# P4_DSPBypass.net
KiCad netlist of a schematic drawn in Altium Designer
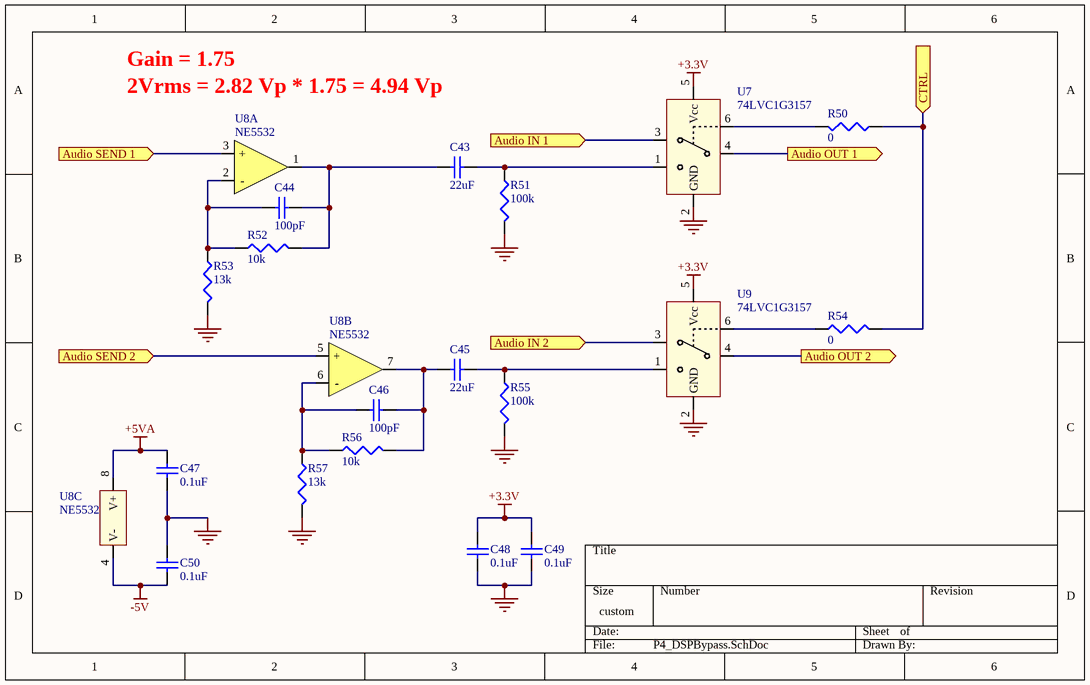
[diagram p0: P4_DSPBypass.SchDoc]

(export (version "E")
  (design (tool "Eeschema 10.0.6"))
  (components
    (comp (ref "C43")
      (value "22uF")
      (footprint "CAP 0603 (1608 metric)")
      (description "Capacitor (Semiconductor SIM Model)")
      (libsource (lib "Miscellaneous Devices") (part "Cap Semi"))
    )
    (comp (ref "C44")
      (value "100pF")
      (footprint "CAP 0603 (1608 metric)")
      (description "Capacitor (Semiconductor SIM Model)")
      (libsource (lib "Miscellaneous Devices") (part "Cap Semi"))
    )
    (comp (ref "C45")
      (value "22uF")
      (footprint "CAP 0603 (1608 metric)")
      (description "Capacitor (Semiconductor SIM Model)")
      (libsource (lib "Miscellaneous Devices") (part "Cap Semi"))
    )
    (comp (ref "C46")
      (value "100pF")
      (footprint "CAP 0603 (1608 metric)")
      (description "Capacitor (Semiconductor SIM Model)")
      (libsource (lib "Miscellaneous Devices") (part "Cap Semi"))
    )
    (comp (ref "C47")
      (value "0.1uF")
      (footprint "CAP 0603 (1608 metric)")
      (description "Capacitor (Semiconductor SIM Model)")
      (libsource (lib "Miscellaneous Devices") (part "Cap Semi"))
    )
    (comp (ref "C48")
      (value "0.1uF")
      (footprint "CAP 0603 (1608 metric)")
      (description "Capacitor (Semiconductor SIM Model)")
      (libsource (lib "Miscellaneous Devices") (part "Cap Semi"))
    )
    (comp (ref "C49")
      (value "0.1uF")
      (footprint "CAP 0603 (1608 metric)")
      (description "Capacitor (Semiconductor SIM Model)")
      (libsource (lib "Miscellaneous Devices") (part "Cap Semi"))
    )
    (comp (ref "C50")
      (value "0.1uF")
      (footprint "CAP 0603 (1608 metric)")
      (description "Capacitor (Semiconductor SIM Model)")
      (libsource (lib "Miscellaneous Devices") (part "Cap Semi"))
    )
    (comp (ref "R50")
      (value "0")
      (footprint "RES 0603 (1608 metric)")
      (description "Resistor")
      (libsource (lib "Miscellaneous Devices") (part "Res3"))
    )
    (comp (ref "R51")
      (value "100k")
      (footprint "RES 0603 (1608 metric)")
      (description "Resistor")
      (libsource (lib "Miscellaneous Devices") (part "Res3"))
    )
    (comp (ref "R52")
      (value "10k")
      (footprint "RES 0603 (1608 metric)")
      (description "Resistor")
      (libsource (lib "Miscellaneous Devices") (part "Res3"))
    )
    (comp (ref "R53")
      (value "13k")
      (footprint "RES 0603 (1608 metric)")
      (description "Resistor")
      (libsource (lib "Miscellaneous Devices") (part "Res3"))
    )
    (comp (ref "R54")
      (value "0")
      (footprint "RES 0603 (1608 metric)")
      (description "Resistor")
      (libsource (lib "Miscellaneous Devices") (part "Res3"))
    )
    (comp (ref "R55")
      (value "100k")
      (footprint "RES 0603 (1608 metric)")
      (description "Resistor")
      (libsource (lib "Miscellaneous Devices") (part "Res3"))
    )
    (comp (ref "R56")
      (value "10k")
      (footprint "RES 0603 (1608 metric)")
      (description "Resistor")
      (libsource (lib "Miscellaneous Devices") (part "Res3"))
    )
    (comp (ref "R57")
      (value "13k")
      (footprint "RES 0603 (1608 metric)")
      (description "Resistor")
      (libsource (lib "Miscellaneous Devices") (part "Res3"))
    )
    (comp (ref "U7")
      (value "74LVC1G3157")
      (description "Single 2:1 Multiplexer")
      (libsource (lib "FilterPoC") (part "74LVC1G3157"))
    )
    (comp (ref "U8")
      (value "NE5532")
      (description "Dual Audio OpAmp")
      (libsource (lib "FilterPoC") (part "NE5532"))
    )
    (comp (ref "U9")
      (value "74LVC1G3157")
      (description "Single 2:1 Multiplexer")
      (libsource (lib "FilterPoC") (part "74LVC1G3157"))
    )
  )
  (nets
    (net (code "1") (name "+3.3V") (class "Default")
      (node (ref "C48") (pin "1") (pinfunction "1_1") (pintype "passive"))
      (node (ref "C49") (pin "1") (pinfunction "1_1") (pintype "passive"))
      (node (ref "U7") (pin "5") (pinfunction "Vcc_5") (pintype "power_in"))
      (node (ref "U9") (pin "5") (pinfunction "Vcc_5") (pintype "power_in"))
    )
    (net (code "2") (name "+5VA") (class "Default")
      (node (ref "C47") (pin "1") (pinfunction "1_1") (pintype "passive"))
      (node (ref "U8") (pin "8") (pinfunction "V+_8") (pintype "power_in"))
    )
    (net (code "3") (name "-5V") (class "Default")
      (node (ref "C50") (pin "2") (pinfunction "2_2") (pintype "passive"))
      (node (ref "U8") (pin "4") (pinfunction "V-_4") (pintype "power_in"))
    )
    (net (code "4") (name "/Audio IN 1") (class "Default")
      (node (ref "U7") (pin "3") (pinfunction "B1_3") (pintype "passive"))
    )
    (net (code "5") (name "/Audio IN 2") (class "Default")
      (node (ref "U9") (pin "3") (pinfunction "B1_3") (pintype "passive"))
    )
    (net (code "6") (name "/Audio OUT 1") (class "Default")
      (node (ref "U7") (pin "4") (pinfunction "A_4") (pintype "passive"))
    )
    (net (code "7") (name "/Audio OUT 2") (class "Default")
      (node (ref "U9") (pin "4") (pinfunction "A_4") (pintype "passive"))
    )
    (net (code "8") (name "/Audio SEND 1") (class "Default")
      (node (ref "U8") (pin "3") (pinfunction "+_3") (pintype "passive"))
    )
    (net (code "9") (name "/Audio SEND 2") (class "Default")
      (node (ref "U8") (pin "5") (pinfunction "+_5") (pintype "passive"))
    )
    (net (code "10") (name "/CTRL") (class "Default")
      (node (ref "R50") (pin "1") (pinfunction "1_1") (pintype "passive"))
      (node (ref "R54") (pin "2") (pinfunction "2_2") (pintype "passive"))
    )
    (net (code "11") (name "GND") (class "Default")
      (node (ref "C47") (pin "2") (pinfunction "2_2") (pintype "passive"))
      (node (ref "C48") (pin "2") (pinfunction "2_2") (pintype "passive"))
      (node (ref "C49") (pin "2") (pinfunction "2_2") (pintype "passive"))
      (node (ref "C50") (pin "1") (pinfunction "1_1") (pintype "passive"))
      (node (ref "R51") (pin "2") (pinfunction "2_2") (pintype "passive"))
      (node (ref "R53") (pin "2") (pinfunction "2_2") (pintype "passive"))
      (node (ref "R55") (pin "2") (pinfunction "2_2") (pintype "passive"))
      (node (ref "R57") (pin "2") (pinfunction "2_2") (pintype "passive"))
      (node (ref "U7") (pin "2") (pinfunction "GND_2") (pintype "power_in"))
      (node (ref "U9") (pin "2") (pinfunction "GND_2") (pintype "power_in"))
    )
    (net (code "12") (name "Net-(U7-B2)") (class "Default")
      (node (ref "C43") (pin "1") (pinfunction "1_1") (pintype "passive"))
      (node (ref "R51") (pin "1") (pinfunction "1_1") (pintype "passive"))
      (node (ref "U7") (pin "1") (pinfunction "B2_1") (pintype "passive"))
    )
    (net (code "13") (name "Net-(U7-S)") (class "Default")
      (node (ref "R50") (pin "2") (pinfunction "2_2") (pintype "passive"))
      (node (ref "U7") (pin "6") (pinfunction "S_6") (pintype "passive"))
    )
    (net (code "14") (name "Net-(U8A--)") (class "Default")
      (node (ref "C44") (pin "1") (pinfunction "1_1") (pintype "passive"))
      (node (ref "R52") (pin "1") (pinfunction "1_1") (pintype "passive"))
      (node (ref "R53") (pin "1") (pinfunction "1_1") (pintype "passive"))
      (node (ref "U8") (pin "2") (pinfunction "-_2") (pintype "passive"))
    )
    (net (code "15") (name "Net-(U8A-OUT)") (class "Default")
      (node (ref "C43") (pin "2") (pinfunction "2_2") (pintype "passive"))
      (node (ref "C44") (pin "2") (pinfunction "2_2") (pintype "passive"))
      (node (ref "R52") (pin "2") (pinfunction "2_2") (pintype "passive"))
      (node (ref "U8") (pin "1") (pinfunction "OUT_1") (pintype "passive"))
    )
    (net (code "16") (name "Net-(U8B--)") (class "Default")
      (node (ref "C46") (pin "1") (pinfunction "1_1") (pintype "passive"))
      (node (ref "R56") (pin "1") (pinfunction "1_1") (pintype "passive"))
      (node (ref "R57") (pin "1") (pinfunction "1_1") (pintype "passive"))
      (node (ref "U8") (pin "6") (pinfunction "-_6") (pintype "passive"))
    )
    (net (code "17") (name "Net-(U8B-OUT)") (class "Default")
      (node (ref "C45") (pin "2") (pinfunction "2_2") (pintype "passive"))
      (node (ref "C46") (pin "2") (pinfunction "2_2") (pintype "passive"))
      (node (ref "R56") (pin "2") (pinfunction "2_2") (pintype "passive"))
      (node (ref "U8") (pin "7") (pinfunction "OUT_7") (pintype "passive"))
    )
    (net (code "18") (name "Net-(U9-B2)") (class "Default")
      (node (ref "C45") (pin "1") (pinfunction "1_1") (pintype "passive"))
      (node (ref "R55") (pin "1") (pinfunction "1_1") (pintype "passive"))
      (node (ref "U9") (pin "1") (pinfunction "B2_1") (pintype "passive"))
    )
    (net (code "19") (name "Net-(U9-S)") (class "Default")
      (node (ref "R54") (pin "1") (pinfunction "1_1") (pintype "passive"))
      (node (ref "U9") (pin "6") (pinfunction "S_6") (pintype "passive"))
    )
  )
)
